# WS2812.net
KiCad netlist of a schematic drawn in Altium Designer
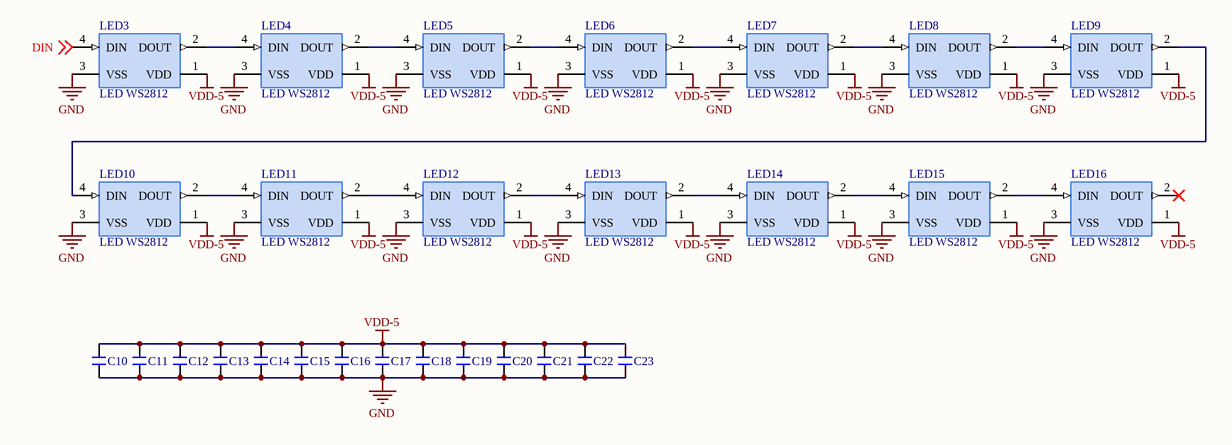
[diagram p0: WS2812.SchDoc]

(export (version "E")
  (design (tool "Eeschema 10.0.6"))
  (components
    (comp (ref "C10")
      (value "~")
      (footprint "C 0805")
      (description "Non-polar patch capacitor")
      (fields (field (name "版权归属") "源创客"))
      (libsource (lib "Passive (Resistor-Capacitor-Inductor-Veristor-Ferrite)") (part "C"))
    )
    (comp (ref "C11")
      (value "~")
      (footprint "C 0805")
      (description "Non-polar patch capacitor")
      (fields (field (name "版权归属") "源创客"))
      (libsource (lib "Passive (Resistor-Capacitor-Inductor-Veristor-Ferrite)") (part "C"))
    )
    (comp (ref "C12")
      (value "~")
      (footprint "C 0805")
      (description "Non-polar patch capacitor")
      (fields (field (name "版权归属") "源创客"))
      (libsource (lib "Passive (Resistor-Capacitor-Inductor-Veristor-Ferrite)") (part "C"))
    )
    (comp (ref "C13")
      (value "~")
      (footprint "C 0805")
      (description "Non-polar patch capacitor")
      (fields (field (name "版权归属") "源创客"))
      (libsource (lib "Passive (Resistor-Capacitor-Inductor-Veristor-Ferrite)") (part "C"))
    )
    (comp (ref "C14")
      (value "~")
      (footprint "C 0805")
      (description "Non-polar patch capacitor")
      (fields (field (name "版权归属") "源创客"))
      (libsource (lib "Passive (Resistor-Capacitor-Inductor-Veristor-Ferrite)") (part "C"))
    )
    (comp (ref "C15")
      (value "~")
      (footprint "C 0805")
      (description "Non-polar patch capacitor")
      (fields (field (name "版权归属") "源创客"))
      (libsource (lib "Passive (Resistor-Capacitor-Inductor-Veristor-Ferrite)") (part "C"))
    )
    (comp (ref "C16")
      (value "~")
      (footprint "C 0805")
      (description "Non-polar patch capacitor")
      (fields (field (name "版权归属") "源创客"))
      (libsource (lib "Passive (Resistor-Capacitor-Inductor-Veristor-Ferrite)") (part "C"))
    )
    (comp (ref "C17")
      (value "~")
      (footprint "C 0805")
      (description "Non-polar patch capacitor")
      (fields (field (name "版权归属") "源创客"))
      (libsource (lib "Passive (Resistor-Capacitor-Inductor-Veristor-Ferrite)") (part "C"))
    )
    (comp (ref "C18")
      (value "~")
      (footprint "C 0805")
      (description "Non-polar patch capacitor")
      (fields (field (name "版权归属") "源创客"))
      (libsource (lib "Passive (Resistor-Capacitor-Inductor-Veristor-Ferrite)") (part "C"))
    )
    (comp (ref "C19")
      (value "~")
      (footprint "C 0805")
      (description "Non-polar patch capacitor")
      (fields (field (name "版权归属") "源创客"))
      (libsource (lib "Passive (Resistor-Capacitor-Inductor-Veristor-Ferrite)") (part "C"))
    )
    (comp (ref "C20")
      (value "~")
      (footprint "C 0805")
      (description "Non-polar patch capacitor")
      (fields (field (name "版权归属") "源创客"))
      (libsource (lib "Passive (Resistor-Capacitor-Inductor-Veristor-Ferrite)") (part "C"))
    )
    (comp (ref "C21")
      (value "~")
      (footprint "C 0805")
      (description "Non-polar patch capacitor")
      (fields (field (name "版权归属") "源创客"))
      (libsource (lib "Passive (Resistor-Capacitor-Inductor-Veristor-Ferrite)") (part "C"))
    )
    (comp (ref "C22")
      (value "~")
      (footprint "C 0805")
      (description "Non-polar patch capacitor")
      (fields (field (name "版权归属") "源创客"))
      (libsource (lib "Passive (Resistor-Capacitor-Inductor-Veristor-Ferrite)") (part "C"))
    )
    (comp (ref "C23")
      (value "~")
      (footprint "C 0805")
      (description "Non-polar patch capacitor")
      (fields (field (name "版权归属") "源创客"))
      (libsource (lib "Passive (Resistor-Capacitor-Inductor-Veristor-Ferrite)") (part "C"))
    )
    (comp (ref "LED3")
      (value "LED WS2812")
      (footprint "LED WS2812 (5050)")
      (libsource (lib "LED") (part "LED WS2812"))
    )
    (comp (ref "LED4")
      (value "LED WS2812")
      (footprint "LED WS2812 (5050)")
      (libsource (lib "LED") (part "LED WS2812"))
    )
    (comp (ref "LED5")
      (value "LED WS2812")
      (footprint "LED WS2812 (5050)")
      (libsource (lib "LED") (part "LED WS2812"))
    )
    (comp (ref "LED6")
      (value "LED WS2812")
      (footprint "LED WS2812 (5050)")
      (libsource (lib "LED") (part "LED WS2812"))
    )
    (comp (ref "LED7")
      (value "LED WS2812")
      (footprint "LED WS2812 (5050)")
      (libsource (lib "LED") (part "LED WS2812"))
    )
    (comp (ref "LED8")
      (value "LED WS2812")
      (footprint "LED WS2812 (5050)")
      (libsource (lib "LED") (part "LED WS2812"))
    )
    (comp (ref "LED9")
      (value "LED WS2812")
      (footprint "LED WS2812 (5050)")
      (libsource (lib "LED") (part "LED WS2812"))
    )
    (comp (ref "LED10")
      (value "LED WS2812")
      (footprint "LED WS2812 (5050)")
      (libsource (lib "LED") (part "LED WS2812"))
    )
    (comp (ref "LED11")
      (value "LED WS2812")
      (footprint "LED WS2812 (5050)")
      (libsource (lib "LED") (part "LED WS2812"))
    )
    (comp (ref "LED12")
      (value "LED WS2812")
      (footprint "LED WS2812 (5050)")
      (libsource (lib "LED") (part "LED WS2812"))
    )
    (comp (ref "LED13")
      (value "LED WS2812")
      (footprint "LED WS2812 (5050)")
      (libsource (lib "LED") (part "LED WS2812"))
    )
    (comp (ref "LED14")
      (value "LED WS2812")
      (footprint "LED WS2812 (5050)")
      (libsource (lib "LED") (part "LED WS2812"))
    )
    (comp (ref "LED15")
      (value "LED WS2812")
      (footprint "LED WS2812 (5050)")
      (libsource (lib "LED") (part "LED WS2812"))
    )
    (comp (ref "LED16")
      (value "LED WS2812")
      (footprint "LED WS2812 (5050)")
      (libsource (lib "LED") (part "LED WS2812"))
    )
  )
  (nets
    (net (code "1") (name "DIN") (class "Default")
      (node (ref "LED3") (pin "4") (pinfunction "DIN_4") (pintype "input"))
    )
    (net (code "2") (name "GND") (class "Default")
      (node (ref "C10") (pin "1") (pinfunction "1_1") (pintype "passive"))
      (node (ref "C11") (pin "1") (pinfunction "1_1") (pintype "passive"))
      (node (ref "C12") (pin "1") (pinfunction "1_1") (pintype "passive"))
      (node (ref "C13") (pin "1") (pinfunction "1_1") (pintype "passive"))
      (node (ref "C14") (pin "1") (pinfunction "1_1") (pintype "passive"))
      (node (ref "C15") (pin "1") (pinfunction "1_1") (pintype "passive"))
      (node (ref "C16") (pin "1") (pinfunction "1_1") (pintype "passive"))
      (node (ref "C17") (pin "1") (pinfunction "1_1") (pintype "passive"))
      (node (ref "C18") (pin "1") (pinfunction "1_1") (pintype "passive"))
      (node (ref "C19") (pin "1") (pinfunction "1_1") (pintype "passive"))
      (node (ref "C20") (pin "1") (pinfunction "1_1") (pintype "passive"))
      (node (ref "C21") (pin "1") (pinfunction "1_1") (pintype "passive"))
      (node (ref "C22") (pin "1") (pinfunction "1_1") (pintype "passive"))
      (node (ref "C23") (pin "1") (pinfunction "1_1") (pintype "passive"))
      (node (ref "LED10") (pin "3") (pinfunction "VSS_3") (pintype "power_in"))
      (node (ref "LED11") (pin "3") (pinfunction "VSS_3") (pintype "power_in"))
      (node (ref "LED12") (pin "3") (pinfunction "VSS_3") (pintype "power_in"))
      (node (ref "LED13") (pin "3") (pinfunction "VSS_3") (pintype "power_in"))
      (node (ref "LED14") (pin "3") (pinfunction "VSS_3") (pintype "power_in"))
      (node (ref "LED15") (pin "3") (pinfunction "VSS_3") (pintype "power_in"))
      (node (ref "LED16") (pin "3") (pinfunction "VSS_3") (pintype "power_in"))
      (node (ref "LED3") (pin "3") (pinfunction "VSS_3") (pintype "power_in"))
      (node (ref "LED4") (pin "3") (pinfunction "VSS_3") (pintype "power_in"))
      (node (ref "LED5") (pin "3") (pinfunction "VSS_3") (pintype "power_in"))
      (node (ref "LED6") (pin "3") (pinfunction "VSS_3") (pintype "power_in"))
      (node (ref "LED7") (pin "3") (pinfunction "VSS_3") (pintype "power_in"))
      (node (ref "LED8") (pin "3") (pinfunction "VSS_3") (pintype "power_in"))
      (node (ref "LED9") (pin "3") (pinfunction "VSS_3") (pintype "power_in"))
    )
    (net (code "3") (name "Net-(LED3-DOUT)") (class "Default")
      (node (ref "LED3") (pin "2") (pinfunction "DOUT_2") (pintype "output"))
      (node (ref "LED4") (pin "4") (pinfunction "DIN_4") (pintype "input"))
    )
    (net (code "4") (name "Net-(LED4-DOUT)") (class "Default")
      (node (ref "LED4") (pin "2") (pinfunction "DOUT_2") (pintype "output"))
      (node (ref "LED5") (pin "4") (pinfunction "DIN_4") (pintype "input"))
    )
    (net (code "5") (name "Net-(LED5-DOUT)") (class "Default")
      (node (ref "LED5") (pin "2") (pinfunction "DOUT_2") (pintype "output"))
      (node (ref "LED6") (pin "4") (pinfunction "DIN_4") (pintype "input"))
    )
    (net (code "6") (name "Net-(LED6-DOUT)") (class "Default")
      (node (ref "LED6") (pin "2") (pinfunction "DOUT_2") (pintype "output"))
      (node (ref "LED7") (pin "4") (pinfunction "DIN_4") (pintype "input"))
    )
    (net (code "7") (name "Net-(LED7-DOUT)") (class "Default")
      (node (ref "LED7") (pin "2") (pinfunction "DOUT_2") (pintype "output"))
      (node (ref "LED8") (pin "4") (pinfunction "DIN_4") (pintype "input"))
    )
    (net (code "8") (name "Net-(LED8-DOUT)") (class "Default")
      (node (ref "LED8") (pin "2") (pinfunction "DOUT_2") (pintype "output"))
      (node (ref "LED9") (pin "4") (pinfunction "DIN_4") (pintype "input"))
    )
    (net (code "9") (name "Net-(LED10-DIN)") (class "Default")
      (node (ref "LED10") (pin "4") (pinfunction "DIN_4") (pintype "input"))
      (node (ref "LED9") (pin "2") (pinfunction "DOUT_2") (pintype "output"))
    )
    (net (code "10") (name "Net-(LED10-DOUT)") (class "Default")
      (node (ref "LED10") (pin "2") (pinfunction "DOUT_2") (pintype "output"))
      (node (ref "LED11") (pin "4") (pinfunction "DIN_4") (pintype "input"))
    )
    (net (code "11") (name "Net-(LED11-DOUT)") (class "Default")
      (node (ref "LED11") (pin "2") (pinfunction "DOUT_2") (pintype "output"))
      (node (ref "LED12") (pin "4") (pinfunction "DIN_4") (pintype "input"))
    )
    (net (code "12") (name "Net-(LED12-DOUT)") (class "Default")
      (node (ref "LED12") (pin "2") (pinfunction "DOUT_2") (pintype "output"))
      (node (ref "LED13") (pin "4") (pinfunction "DIN_4") (pintype "input"))
    )
    (net (code "13") (name "Net-(LED13-DOUT)") (class "Default")
      (node (ref "LED13") (pin "2") (pinfunction "DOUT_2") (pintype "output"))
      (node (ref "LED14") (pin "4") (pinfunction "DIN_4") (pintype "input"))
    )
    (net (code "14") (name "Net-(LED14-DOUT)") (class "Default")
      (node (ref "LED14") (pin "2") (pinfunction "DOUT_2") (pintype "output"))
      (node (ref "LED15") (pin "4") (pinfunction "DIN_4") (pintype "input"))
    )
    (net (code "15") (name "Net-(LED15-DOUT)") (class "Default")
      (node (ref "LED15") (pin "2") (pinfunction "DOUT_2") (pintype "output"))
      (node (ref "LED16") (pin "4") (pinfunction "DIN_4") (pintype "input"))
    )
    (net (code "16") (name "VDD-5") (class "Default")
      (node (ref "C10") (pin "2") (pinfunction "2_2") (pintype "passive"))
      (node (ref "C11") (pin "2") (pinfunction "2_2") (pintype "passive"))
      (node (ref "C12") (pin "2") (pinfunction "2_2") (pintype "passive"))
      (node (ref "C13") (pin "2") (pinfunction "2_2") (pintype "passive"))
      (node (ref "C14") (pin "2") (pinfunction "2_2") (pintype "passive"))
      (node (ref "C15") (pin "2") (pinfunction "2_2") (pintype "passive"))
      (node (ref "C16") (pin "2") (pinfunction "2_2") (pintype "passive"))
      (node (ref "C17") (pin "2") (pinfunction "2_2") (pintype "passive"))
      (node (ref "C18") (pin "2") (pinfunction "2_2") (pintype "passive"))
      (node (ref "C19") (pin "2") (pinfunction "2_2") (pintype "passive"))
      (node (ref "C20") (pin "2") (pinfunction "2_2") (pintype "passive"))
      (node (ref "C21") (pin "2") (pinfunction "2_2") (pintype "passive"))
      (node (ref "C22") (pin "2") (pinfunction "2_2") (pintype "passive"))
      (node (ref "C23") (pin "2") (pinfunction "2_2") (pintype "passive"))
      (node (ref "LED10") (pin "1") (pinfunction "VDD_1") (pintype "power_in"))
      (node (ref "LED11") (pin "1") (pinfunction "VDD_1") (pintype "power_in"))
      (node (ref "LED12") (pin "1") (pinfunction "VDD_1") (pintype "power_in"))
      (node (ref "LED13") (pin "1") (pinfunction "VDD_1") (pintype "power_in"))
      (node (ref "LED14") (pin "1") (pinfunction "VDD_1") (pintype "power_in"))
      (node (ref "LED15") (pin "1") (pinfunction "VDD_1") (pintype "power_in"))
      (node (ref "LED16") (pin "1") (pinfunction "VDD_1") (pintype "power_in"))
      (node (ref "LED3") (pin "1") (pinfunction "VDD_1") (pintype "power_in"))
      (node (ref "LED4") (pin "1") (pinfunction "VDD_1") (pintype "power_in"))
      (node (ref "LED5") (pin "1") (pinfunction "VDD_1") (pintype "power_in"))
      (node (ref "LED6") (pin "1") (pinfunction "VDD_1") (pintype "power_in"))
      (node (ref "LED7") (pin "1") (pinfunction "VDD_1") (pintype "power_in"))
      (node (ref "LED8") (pin "1") (pinfunction "VDD_1") (pintype "power_in"))
      (node (ref "LED9") (pin "1") (pinfunction "VDD_1") (pintype "power_in"))
    )
    (net (code "17") (name "unconnected-(LED16-DOUT-Pad2)") (class "Default")
      (node (ref "LED16") (pin "2") (pinfunction "DOUT_2") (pintype "output+no_connect"))
    )
  )
)
